# 2Leonardo_PCB.net
KiCad netlist of a schematic drawn in Altium Designer
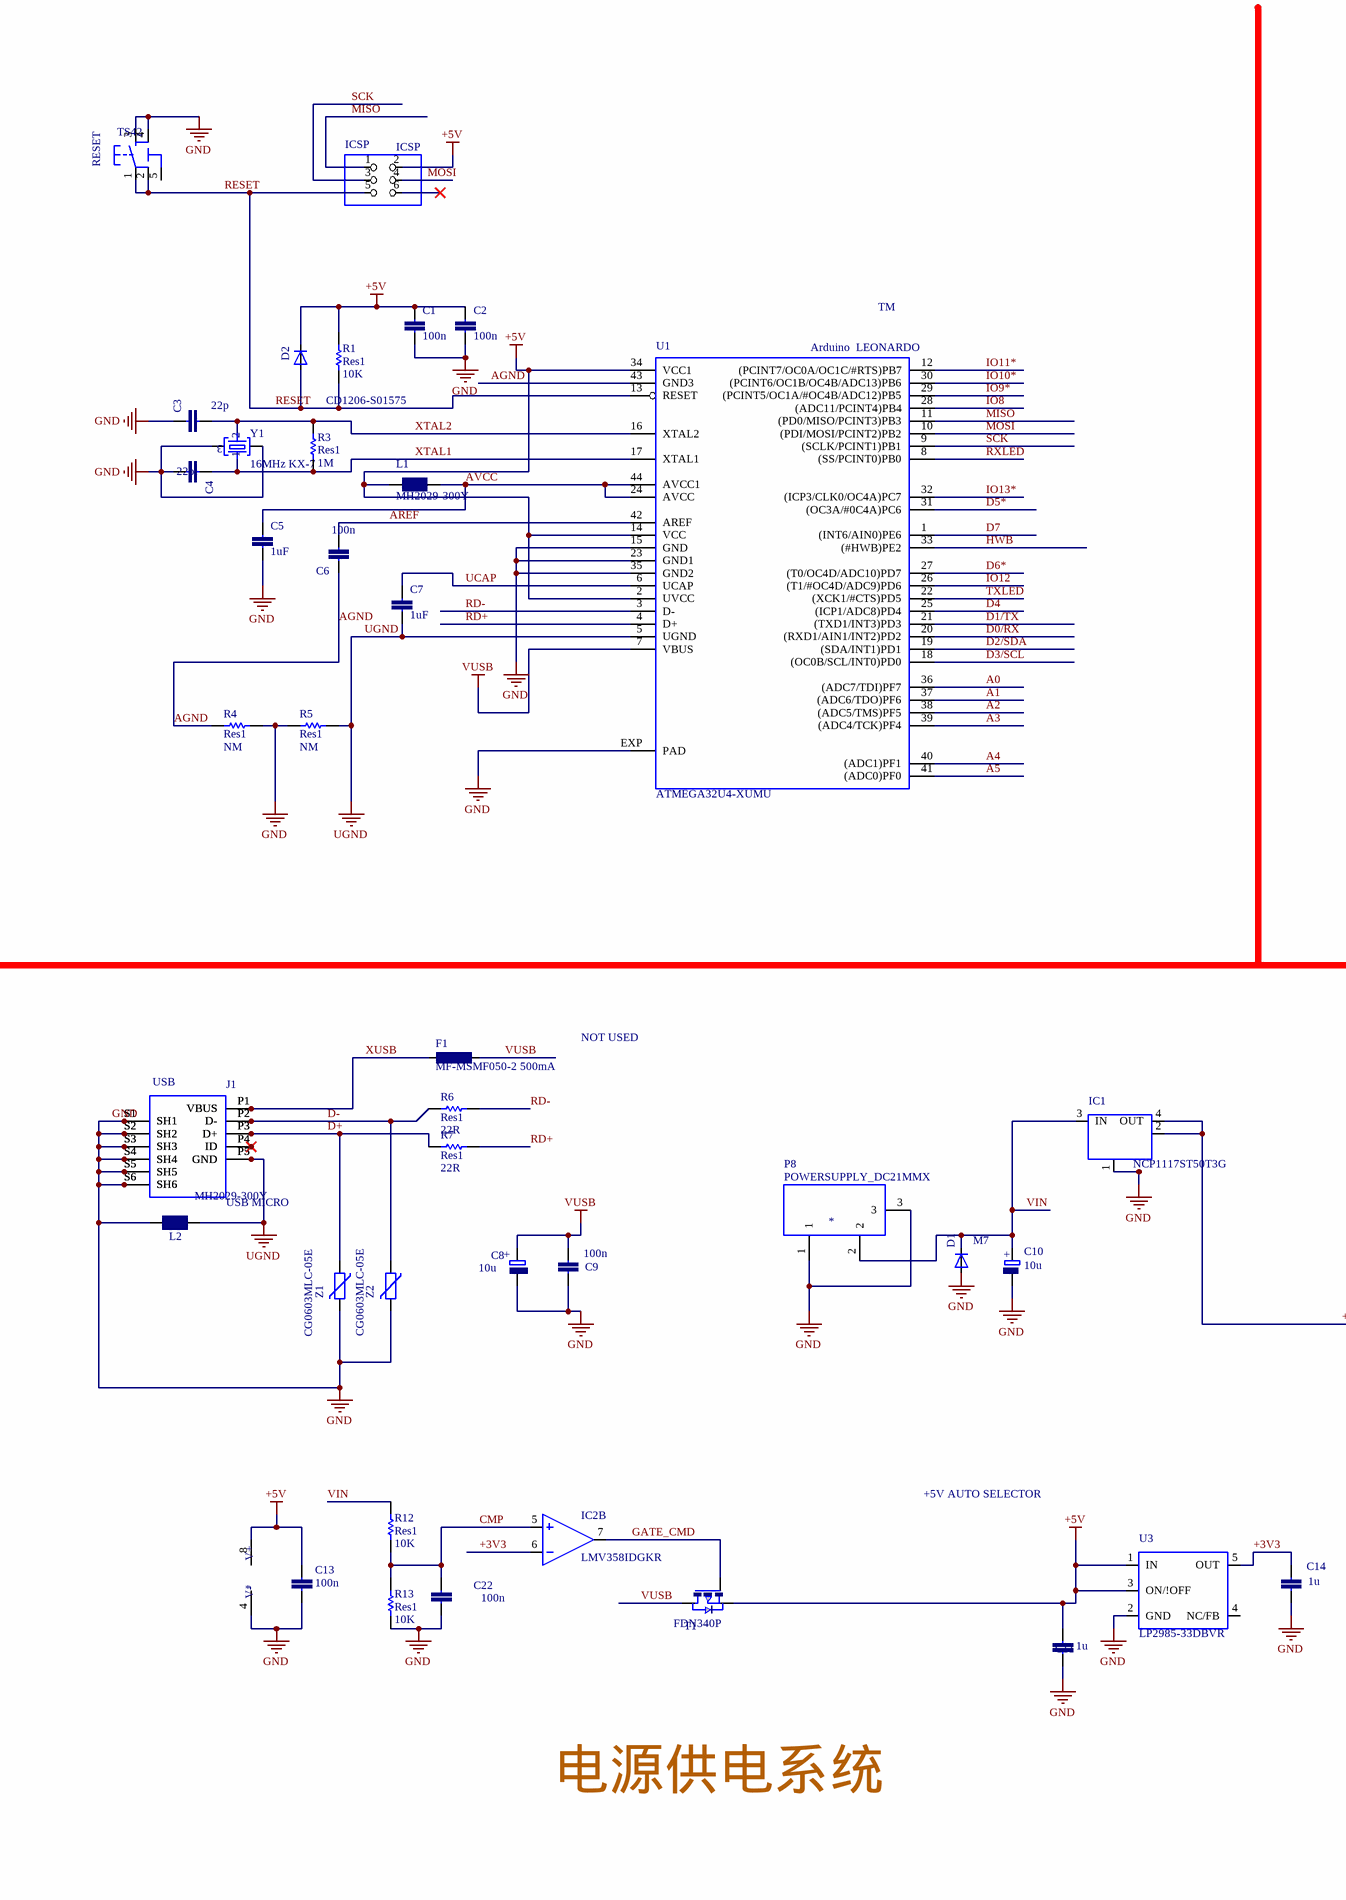
[diagram p0: 2Leonardo_PCB.SchDoc, left]
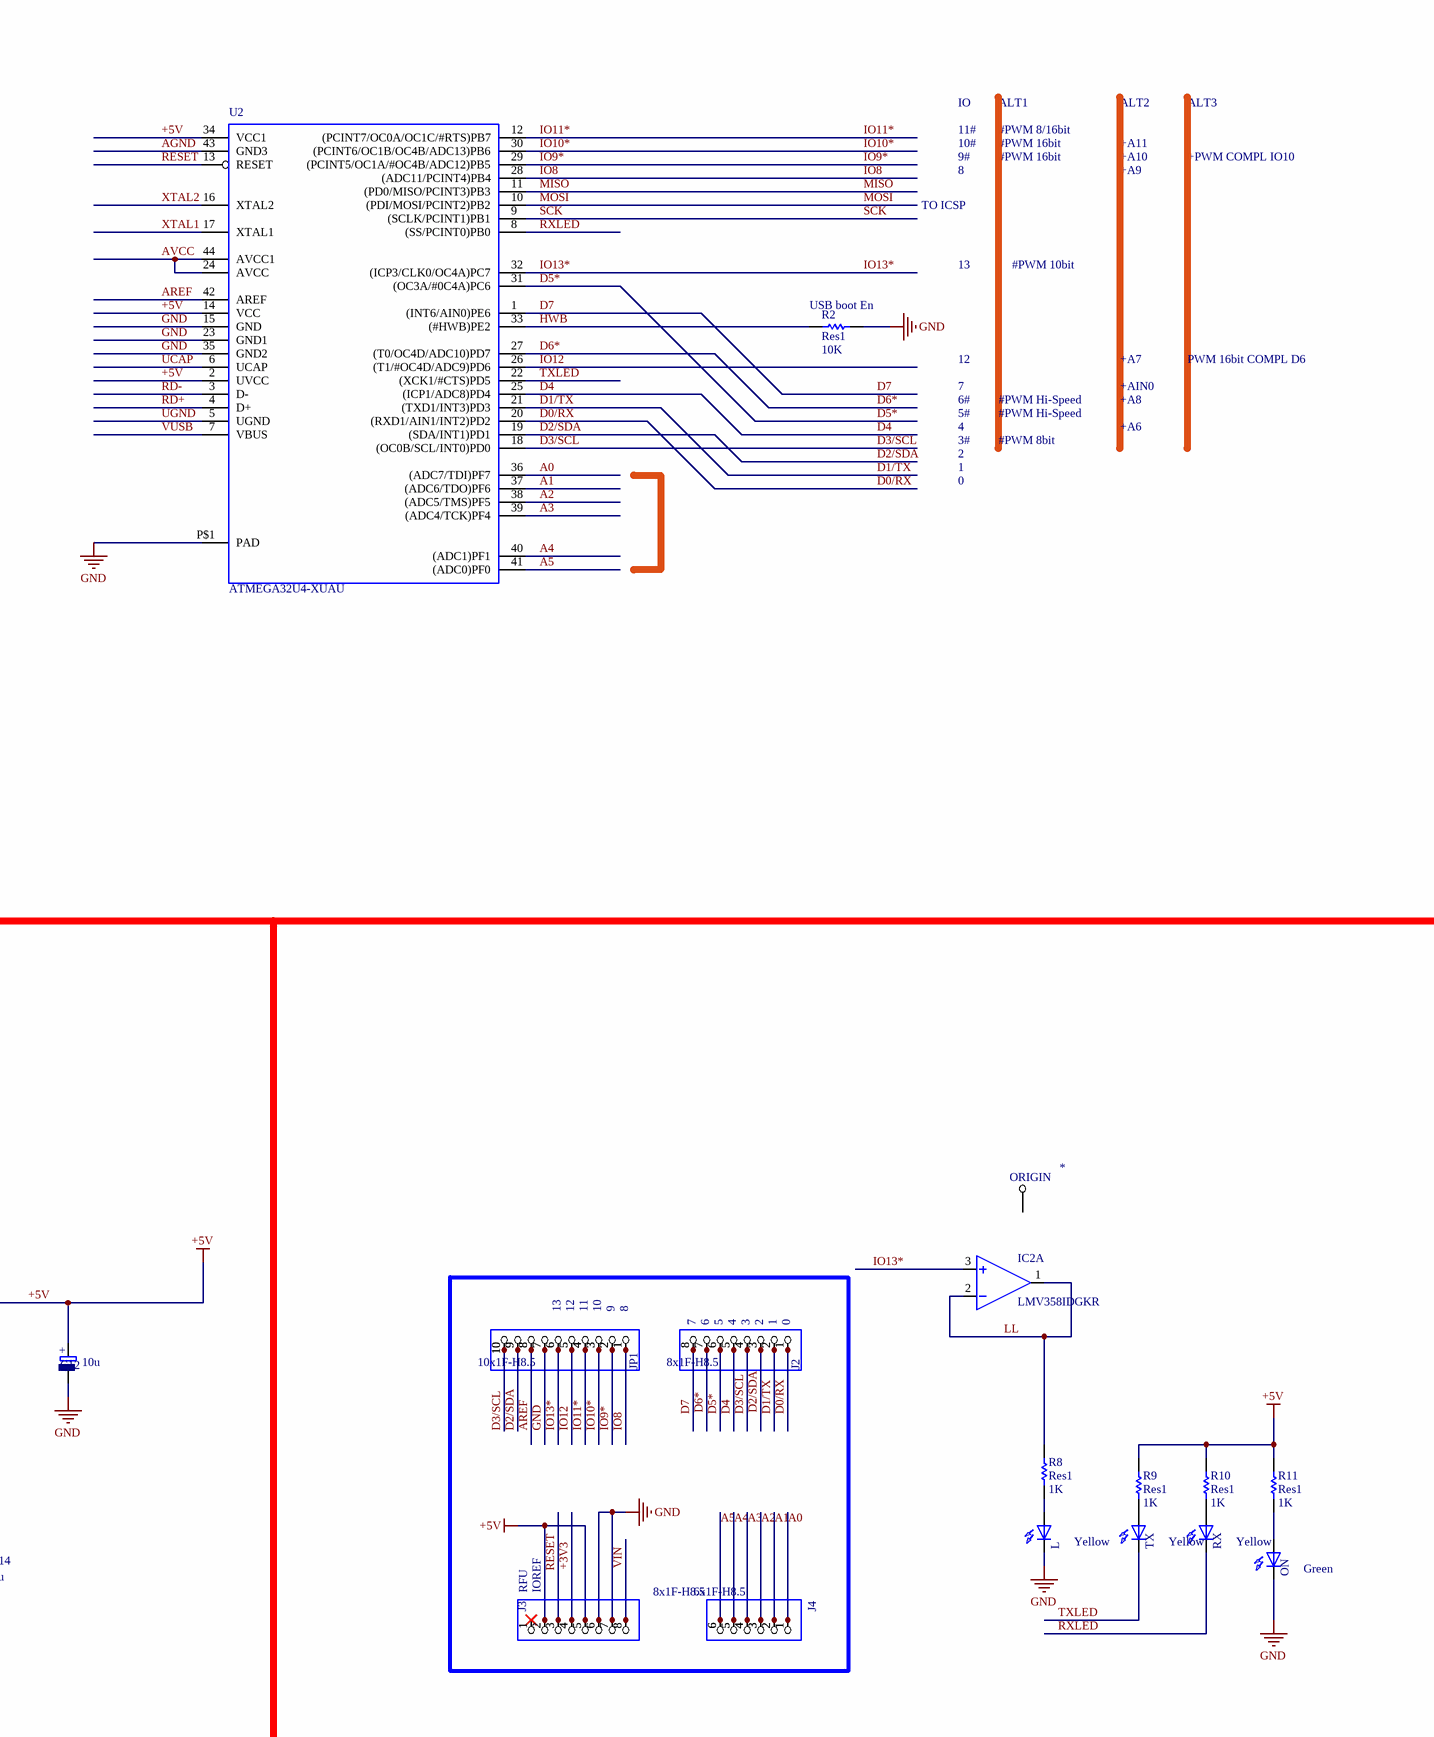
[diagram p1: 2Leonardo_PCB.SchDoc, right]

(export (version "E")
  (design (tool "Eeschema 10.0.6"))
  (components
    (comp (ref "C1") (value "100n") (footprint "C0603-ROUND") (libsource (lib "SmartPrj") (part "C-EUC0603")))
    (comp (ref "C2") (value "100n") (footprint "C0603-ROUND") (libsource (lib "SmartPrj") (part "C-EUC0603")))
    (comp (ref "C3") (value "22p") (footprint "C0603-ROUND") (libsource (lib "") (part "C-EUC0603_3")))
    (comp (ref "C4") (value "22p") (footprint "C0603-ROUND") (libsource (lib "") (part "C-EUC0603_1")))
    (comp (ref "C5") (value "1uF") (footprint "C0603-ROUND") (libsource (lib "SmartPrj") (part "C-EUC0603")))
    (comp (ref "C6") (value "100n") (footprint "C0603-ROUND") (libsource (lib "") (part "C-EUC0603_2")))
    (comp (ref "C7") (value "1uF") (footprint "C0603-ROUND") (libsource (lib "SmartPrj") (part "C-EUC0603")))
    (comp (ref "C8") (value "10u") (footprint "SMC_B") (libsource (lib "rcl") (part "CPOL-EUSMCB")))
    (comp (ref "C9") (value "100n") (footprint "C0603-ROUND") (libsource (lib "") (part "C-EUC0603_3")))
    (comp (ref "C10") (value "10u") (footprint "SMC_B") (libsource (lib "") (part "CPOL-EUSMCB_1")))
    (comp (ref "C11") (value "1u") (footprint "C0603-ROUND") (libsource (lib "") (part "C-EUC0603_3")))
    (comp (ref "C12") (value "10u") (footprint "SMC_B") (libsource (lib "") (part "CPOL-EUSMCB_1")))
    (comp (ref "C13")
      (value "100n")
      (footprint "C0603-ROUND")
      (libsource (lib "SmartPrj") (part "C-EUC0603"))
    )
    (comp (ref "C14") (value "1u") (footprint "C0603-ROUND") (libsource (lib "") (part "C-EUC0603_2")))
    (comp (ref "C22") (value "100n") (footprint "C0603-ROUND") (libsource (lib "") (part "C-EUC0603_3")))
    (comp (ref "D1") (value "M7") (footprint "SMB") (libsource (lib "diode") (part "DIODE-SMB")))
    (comp (ref "D2")
      (value "CD1206-S01575")
      (footprint "MINIMELF")
      (libsource (lib "diode") (part "DIODE-MINIMELF"))
    )
    (comp (ref "F1")
      (value "MF-MSMF050-2 500mA")
      (footprint "L1812")
      (libsource (lib "rcl") (part "L-EUL1812"))
    )
    (comp (ref "IC1")
      (value "NCP1117ST50T3G")
      (footprint "SOT223")
      (libsource (lib "linear") (part "MC33269ST-3.3T3"))
    )
    (comp (ref "IC2")
      (value "LMV358IDGKR")
      (footprint "MSOP08")
      (libsource (lib "linear") (part "LMV358MMX"))
    )
    (comp (ref "ICSP") (value "ICSP") (footprint "2X03") (libsource (lib "SmartPrj") (part "PINHD-2X3")))
    (comp (ref "J1")
      (value "USB MICRO")
      (footprint "CON2_USB_MICRO_B_AT")
      (libsource (lib "SmartPrj") (part "MYCON2_USB-MINI-B"))
    )
    (comp (ref "J2") (value "8x1F-H8.5") (footprint "1X08") (libsource (lib "SmartPrj") (part "PINHD-1X8")))
    (comp (ref "J3") (value "8x1F-H8.5") (footprint "1X08") (libsource (lib "SmartPrj") (part "PINHD-1X8")))
    (comp (ref "J4") (value "6x1F-H8.5") (footprint "1X06") (libsource (lib "SmartPrj") (part "PINHD-1X6")))
    (comp (ref "JP1")
      (value "10x1F-H8.5")
      (footprint "1X10")
      (libsource (lib "SmartPrj") (part "PINHD-1X10"))
    )
    (comp (ref "L")
      (value "Yellow")
      (footprint "CHIPLED_0805")
      (libsource (lib "led") (part "LEDCHIPLED_0805"))
    )
    (comp (ref "L1") (value "MH2029-300Y") (footprint "0805") (libsource (lib "") (part "WE-CBF_0805_1")))
    (comp (ref "L2")
      (value "MH2029-300Y")
      (footprint "0805")
      (libsource (lib "wuerth-elektronik") (part "WE-CBF_0805"))
    )
    (comp (ref "ON")
      (value "Green")
      (footprint "CHIPLED_0805")
      (libsource (lib "led") (part "LEDCHIPLED_0805"))
    )
    (comp (ref "ORIGIN") (value "*") (footprint "FIDUCIA-MOUNT") (libsource (lib "SmartPrj") (part "TP_SP")))
    (comp (ref "P8")
      (value "*")
      (footprint "POWERSUPPLY_DC-21MM")
      (libsource (lib "SmartPrj") (part "POWERSUPPLY_DC21MMX"))
    )
    (comp (ref "R1")
      (value "Res1")
      (footprint "R0603-ROUND")
      (description "Resistor")
      (fields (field (name "ALTIUM_VALUE") "10K") (field (name "PUBLISHER") "Altium Limited"))
      (libsource (lib "Miscellaneous Devices") (part "Res1"))
    )
    (comp (ref "R2")
      (value "Res1")
      (footprint "R0603-ROUND")
      (description "Resistor")
      (fields (field (name "ALTIUM_VALUE") "10K") (field (name "PUBLISHER") "Altium Limited"))
      (libsource (lib "Miscellaneous Devices") (part "Res1"))
    )
    (comp (ref "R3")
      (value "Res1")
      (footprint "R0603-ROUND")
      (description "Resistor")
      (fields (field (name "ALTIUM_VALUE") "1M") (field (name "PUBLISHER") "Altium Limited"))
      (libsource (lib "Miscellaneous Devices") (part "Res1"))
    )
    (comp (ref "R4")
      (value "Res1")
      (footprint "R0603-ROUND")
      (description "Resistor")
      (fields (field (name "ALTIUM_VALUE") "NM") (field (name "PUBLISHER") "Altium Limited"))
      (libsource (lib "Miscellaneous Devices") (part "Res1"))
    )
    (comp (ref "R5")
      (value "Res1")
      (footprint "R0603-ROUND")
      (description "Resistor")
      (fields (field (name "ALTIUM_VALUE") "NM") (field (name "PUBLISHER") "Altium Limited"))
      (libsource (lib "Miscellaneous Devices") (part "Res1"))
    )
    (comp (ref "R6")
      (value "Res1")
      (footprint "R0603-ROUND")
      (description "Resistor")
      (fields (field (name "ALTIUM_VALUE") "22R") (field (name "PUBLISHER") "Altium Limited"))
      (libsource (lib "Miscellaneous Devices") (part "Res1"))
    )
    (comp (ref "R7")
      (value "Res1")
      (footprint "R0603-ROUND")
      (description "Resistor")
      (fields (field (name "ALTIUM_VALUE") "22R") (field (name "PUBLISHER") "Altium Limited"))
      (libsource (lib "Miscellaneous Devices") (part "Res1"))
    )
    (comp (ref "R8")
      (value "Res1")
      (footprint "R0603-ROUND")
      (description "Resistor")
      (fields (field (name "ALTIUM_VALUE") "1K") (field (name "PUBLISHER") "Altium Limited"))
      (libsource (lib "Miscellaneous Devices") (part "Res1"))
    )
    (comp (ref "R9")
      (value "Res1")
      (footprint "R0603-ROUND")
      (description "Resistor")
      (fields (field (name "ALTIUM_VALUE") "1K") (field (name "PUBLISHER") "Altium Limited"))
      (libsource (lib "Miscellaneous Devices") (part "Res1"))
    )
    (comp (ref "R10")
      (value "Res1")
      (footprint "R0603-ROUND")
      (description "Resistor")
      (fields (field (name "ALTIUM_VALUE") "1K") (field (name "PUBLISHER") "Altium Limited"))
      (libsource (lib "Miscellaneous Devices") (part "Res1"))
    )
    (comp (ref "R11")
      (value "Res1")
      (footprint "R0603-ROUND")
      (description "Resistor")
      (fields (field (name "ALTIUM_VALUE") "1K") (field (name "PUBLISHER") "Altium Limited"))
      (libsource (lib "Miscellaneous Devices") (part "Res1"))
    )
    (comp (ref "R12")
      (value "Res1")
      (footprint "R0603-ROUND")
      (description "Resistor")
      (fields (field (name "ALTIUM_VALUE") "10K") (field (name "PUBLISHER") "Altium Limited"))
      (libsource (lib "Miscellaneous Devices") (part "Res1"))
    )
    (comp (ref "R13")
      (value "Res1")
      (footprint "R0603-ROUND")
      (description "Resistor")
      (fields (field (name "ALTIUM_VALUE") "10K") (field (name "PUBLISHER") "Altium Limited"))
      (libsource (lib "Miscellaneous Devices") (part "Res1"))
    )
    (comp (ref "RESET") (value "TS42") (footprint "TS42") (libsource (lib "SmartPrj") (part "TS42")))
    (comp (ref "RX")
      (value "Yellow")
      (footprint "CHIPLED_0805")
      (libsource (lib "led") (part "LEDCHIPLED_0805"))
    )
    (comp (ref "T1") (value "FDN340P") (footprint "SOT-23") (libsource (lib "zetex") (part "PMOSSOT23")))
    (comp (ref "TX")
      (value "Yellow")
      (footprint "CHIPLED_0805")
      (libsource (lib "led") (part "LEDCHIPLED_0805"))
    )
    (comp (ref "U1")
      (value "ATMEGA32U4-XUMU")
      (footprint "QFN44ML7X7")
      (libsource (lib "SmartPrj") (part "ATMEGA32U4-XUMU"))
    )
    (comp (ref "U2")
      (value "ATMEGA32U4-XUAU")
      (footprint "TQFP44-PAD")
      (libsource (lib "SmartPrj") (part "ATMEGA32U4-XUAU"))
    )
    (comp (ref "U3")
      (value "LP2985-33DBVR")
      (footprint "SOT23-DBV")
      (libsource (lib "SmartPrj") (part "LP2985-XXDBVR33"))
    )
    (comp (ref "Y1")
      (value "16MHz KX-7")
      (footprint "CRYSTAL-3.2-2.5")
      (libsource (lib "SmartPrj") (part "CRYSTAL-3.2-2.5"))
    )
    (comp (ref "Z1")
      (value "CG0603MLC-05E")
      (footprint "CT/CN0603")
      (libsource (lib "varistor") (part "VARISTORCN0603"))
    )
    (comp (ref "Z2")
      (value "CG0603MLC-05E")
      (footprint "CT/CN0603")
      (libsource (lib "varistor") (part "VARISTORCN0603"))
    )
  )
  (nets
    (net (code "1") (name "+5V") (class "Default")
      (node (ref "C1") (pin "1") (pinfunction "1_1") (pintype "passive"))
      (node (ref "C11") (pin "2") (pinfunction "2_2") (pintype "passive"))
      (node (ref "C12") (pin "+") (pinfunction "+_+") (pintype "passive"))
      (node (ref "C13") (pin "1") (pinfunction "1_1") (pintype "passive"))
      (node (ref "C2") (pin "1") (pinfunction "1_1") (pintype "passive"))
      (node (ref "D2") (pin "C") (pinfunction "C_C") (pintype "passive"))
      (node (ref "IC1") (pin "2") (pinfunction "OUT@1_2") (pintype "passive"))
      (node (ref "IC1") (pin "4") (pinfunction "OUT_4") (pintype "passive"))
      (node (ref "IC2") (pin "8") (pinfunction "V+_8") (pintype "passive"))
      (node (ref "ICSP") (pin "2") (pinfunction "2_2") (pintype "passive"))
      (node (ref "J3") (pin "2") (pinfunction "2_2") (pintype "passive"))
      (node (ref "J3") (pin "5") (pinfunction "5_5") (pintype "passive"))
      (node (ref "L1") (pin "1") (pinfunction "1_1") (pintype "passive"))
      (node (ref "R1") (pin "2") (pinfunction "2_2") (pintype "passive"))
      (node (ref "R10") (pin "2") (pinfunction "2_2") (pintype "passive"))
      (node (ref "R11") (pin "2") (pinfunction "2_2") (pintype "passive"))
      (node (ref "R9") (pin "2") (pinfunction "2_2") (pintype "passive"))
      (node (ref "T1") (pin "2") (pinfunction "S_2") (pintype "passive"))
      (node (ref "U1") (pin "14") (pinfunction "VCC_14") (pintype "passive"))
      (node (ref "U1") (pin "2") (pinfunction "UVCC_2") (pintype "passive"))
      (node (ref "U1") (pin "34") (pinfunction "VCC1_34") (pintype "passive"))
      (node (ref "U2") (pin "14") (pinfunction "VCC_14") (pintype "passive"))
      (node (ref "U2") (pin "2") (pinfunction "UVCC_2") (pintype "passive"))
      (node (ref "U2") (pin "34") (pinfunction "VCC1_34") (pintype "passive"))
      (node (ref "U3") (pin "1") (pinfunction "IN_1") (pintype "passive"))
      (node (ref "U3") (pin "3") (pinfunction "ON/!OFF_3") (pintype "passive"))
    )
    (net (code "2") (name "/+3V3") (class "Default")
      (node (ref "C14") (pin "2") (pinfunction "2_2") (pintype "passive"))
      (node (ref "IC2") (pin "6") (pinfunction "-IN_6") (pintype "passive"))
      (node (ref "J3") (pin "4") (pinfunction "4_4") (pintype "passive"))
      (node (ref "U3") (pin "5") (pinfunction "OUT_5") (pintype "passive"))
    )
    (net (code "3") (name "/A0") (class "Default")
      (node (ref "J4") (pin "1") (pinfunction "1_1") (pintype "passive"))
      (node (ref "U1") (pin "36") (pinfunction "(ADC7/TDI)PF7_36") (pintype "passive"))
      (node (ref "U2") (pin "36") (pinfunction "(ADC7/TDI)PF7_36") (pintype "passive"))
    )
    (net (code "4") (name "/A1") (class "Default")
      (node (ref "J4") (pin "2") (pinfunction "2_2") (pintype "passive"))
      (node (ref "U1") (pin "37") (pinfunction "(ADC6/TDO)PF6_37") (pintype "passive"))
      (node (ref "U2") (pin "37") (pinfunction "(ADC6/TDO)PF6_37") (pintype "passive"))
    )
    (net (code "5") (name "/A2") (class "Default")
      (node (ref "J4") (pin "3") (pinfunction "3_3") (pintype "passive"))
      (node (ref "U1") (pin "38") (pinfunction "(ADC5/TMS)PF5_38") (pintype "passive"))
      (node (ref "U2") (pin "38") (pinfunction "(ADC5/TMS)PF5_38") (pintype "passive"))
    )
    (net (code "6") (name "/A3") (class "Default")
      (node (ref "J4") (pin "4") (pinfunction "4_4") (pintype "passive"))
      (node (ref "U1") (pin "39") (pinfunction "(ADC4/TCK)PF4_39") (pintype "passive"))
      (node (ref "U2") (pin "39") (pinfunction "(ADC4/TCK)PF4_39") (pintype "passive"))
    )
    (net (code "7") (name "/A4") (class "Default")
      (node (ref "J4") (pin "5") (pinfunction "5_5") (pintype "passive"))
      (node (ref "U1") (pin "40") (pinfunction "(ADC1)PF1_40") (pintype "passive"))
      (node (ref "U2") (pin "40") (pinfunction "(ADC1)PF1_40") (pintype "passive"))
    )
    (net (code "8") (name "/A5") (class "Default")
      (node (ref "J4") (pin "6") (pinfunction "6_6") (pintype "passive"))
      (node (ref "U1") (pin "41") (pinfunction "(ADC0)PF0_41") (pintype "passive"))
      (node (ref "U2") (pin "41") (pinfunction "(ADC0)PF0_41") (pintype "passive"))
    )
    (net (code "9") (name "/AGND") (class "Default")
      (node (ref "C6") (pin "1") (pinfunction "1_1") (pintype "passive"))
      (node (ref "R4") (pin "1") (pinfunction "1_1") (pintype "passive"))
      (node (ref "U1") (pin "43") (pinfunction "GND3_43") (pintype "passive"))
      (node (ref "U2") (pin "43") (pinfunction "GND3_43") (pintype "passive"))
    )
    (net (code "10") (name "/AREF") (class "Default")
      (node (ref "C6") (pin "2") (pinfunction "2_2") (pintype "passive"))
      (node (ref "JP1") (pin "8") (pinfunction "8_8") (pintype "passive"))
      (node (ref "U1") (pin "42") (pinfunction "AREF_42") (pintype "passive"))
      (node (ref "U2") (pin "42") (pinfunction "AREF_42") (pintype "passive"))
    )
    (net (code "11") (name "/AVCC") (class "Default")
      (node (ref "C5") (pin "1") (pinfunction "1_1") (pintype "passive"))
      (node (ref "L1") (pin "2") (pinfunction "2_2") (pintype "passive"))
      (node (ref "U1") (pin "24") (pinfunction "AVCC_24") (pintype "passive"))
      (node (ref "U1") (pin "44") (pinfunction "AVCC1_44") (pintype "passive"))
      (node (ref "U2") (pin "24") (pinfunction "AVCC_24") (pintype "passive"))
      (node (ref "U2") (pin "44") (pinfunction "AVCC1_44") (pintype "passive"))
    )
    (net (code "12") (name "/CMP") (class "Default")
      (node (ref "C22") (pin "2") (pinfunction "2_2") (pintype "passive"))
      (node (ref "IC2") (pin "5") (pinfunction "+IN_5") (pintype "passive"))
      (node (ref "R12") (pin "1") (pinfunction "1_1") (pintype "passive"))
      (node (ref "R13") (pin "2") (pinfunction "2_2") (pintype "passive"))
    )
    (net (code "13") (name "/D+") (class "Default")
      (node (ref "J1") (pin "P3") (pinfunction "D+_P3") (pintype "passive"))
      (node (ref "R7") (pin "1") (pinfunction "1_1") (pintype "passive"))
      (node (ref "Z1") (pin "1") (pinfunction "1_1") (pintype "passive"))
    )
    (net (code "14") (name "/D-") (class "Default")
      (node (ref "J1") (pin "P2") (pinfunction "D-_P2") (pintype "passive"))
      (node (ref "R6") (pin "1") (pinfunction "1_1") (pintype "passive"))
      (node (ref "Z2") (pin "1") (pinfunction "1_1") (pintype "passive"))
    )
    (net (code "15") (name "/D0{slash}RX") (class "Default")
      (node (ref "J2") (pin "1") (pinfunction "1_1") (pintype "passive"))
      (node (ref "U1") (pin "20") (pinfunction "(RXD1/AIN1/INT2)PD2_20") (pintype "passive"))
      (node (ref "U2") (pin "20") (pinfunction "(RXD1/AIN1/INT2)PD2_20") (pintype "passive"))
    )
    (net (code "16") (name "/D1{slash}TX") (class "Default")
      (node (ref "J2") (pin "2") (pinfunction "2_2") (pintype "passive"))
      (node (ref "U1") (pin "21") (pinfunction "(TXD1/INT3)PD3_21") (pintype "passive"))
      (node (ref "U2") (pin "21") (pinfunction "(TXD1/INT3)PD3_21") (pintype "passive"))
    )
    (net (code "17") (name "/D2{slash}SDA") (class "Default")
      (node (ref "J2") (pin "3") (pinfunction "3_3") (pintype "passive"))
      (node (ref "JP1") (pin "9") (pinfunction "9_9") (pintype "passive"))
      (node (ref "U1") (pin "19") (pinfunction "(SDA/INT1)PD1_19") (pintype "passive"))
      (node (ref "U2") (pin "19") (pinfunction "(SDA/INT1)PD1_19") (pintype "passive"))
    )
    (net (code "18") (name "/D3{slash}SCL") (class "Default")
      (node (ref "J2") (pin "4") (pinfunction "4_4") (pintype "passive"))
      (node (ref "JP1") (pin "10") (pinfunction "10_10") (pintype "passive"))
      (node (ref "U1") (pin "18") (pinfunction "(OC0B/SCL/INT0)PD0_18") (pintype "passive"))
      (node (ref "U2") (pin "18") (pinfunction "(OC0B/SCL/INT0)PD0_18") (pintype "passive"))
    )
    (net (code "19") (name "/D4") (class "Default")
      (node (ref "J2") (pin "5") (pinfunction "5_5") (pintype "passive"))
      (node (ref "U1") (pin "25") (pinfunction "(ICP1/ADC8)PD4_25") (pintype "passive"))
      (node (ref "U2") (pin "25") (pinfunction "(ICP1/ADC8)PD4_25") (pintype "passive"))
    )
    (net (code "20") (name "/D5*") (class "Default")
      (node (ref "J2") (pin "6") (pinfunction "6_6") (pintype "passive"))
      (node (ref "U1") (pin "31") (pinfunction "(OC3A/#0C4A)PC6_31") (pintype "passive"))
      (node (ref "U2") (pin "31") (pinfunction "(OC3A/#0C4A)PC6_31") (pintype "passive"))
    )
    (net (code "21") (name "/D6*") (class "Default")
      (node (ref "J2") (pin "7") (pinfunction "7_7") (pintype "passive"))
      (node (ref "U1") (pin "27") (pinfunction "(T0/OC4D/ADC10)PD7_27") (pintype "passive"))
      (node (ref "U2") (pin "27") (pinfunction "(T0/OC4D/ADC10)PD7_27") (pintype "passive"))
    )
    (net (code "22") (name "/D7") (class "Default")
      (node (ref "J2") (pin "8") (pinfunction "8_8") (pintype "passive"))
      (node (ref "U1") (pin "1") (pinfunction "(INT6/AIN0)PE6_1") (pintype "passive"))
      (node (ref "U2") (pin "1") (pinfunction "(INT6/AIN0)PE6_1") (pintype "passive"))
    )
    (net (code "23") (name "/GATE_CMD") (class "Default")
      (node (ref "IC2") (pin "7") (pinfunction "OUT_7") (pintype "passive"))
      (node (ref "T1") (pin "3") (pinfunction "G_3") (pintype "passive"))
    )
    (net (code "24") (name "/HWB") (class "Default")
      (node (ref "R2") (pin "2") (pinfunction "2_2") (pintype "passive"))
      (node (ref "U1") (pin "33") (pinfunction "(#HWB)PE2_33") (pintype "passive"))
      (node (ref "U2") (pin "33") (pinfunction "(#HWB)PE2_33") (pintype "passive"))
    )
    (net (code "25") (name "/IO8") (class "Default")
      (node (ref "JP1") (pin "1") (pinfunction "1_1") (pintype "passive"))
      (node (ref "U1") (pin "28") (pinfunction "(ADC11/PCINT4)PB4_28") (pintype "passive"))
      (node (ref "U2") (pin "28") (pinfunction "(ADC11/PCINT4)PB4_28") (pintype "passive"))
    )
    (net (code "26") (name "/IO9*") (class "Default")
      (node (ref "JP1") (pin "2") (pinfunction "2_2") (pintype "passive"))
      (node (ref "U1") (pin "29") (pinfunction "(PCINT5/OC1A/#OC4B/ADC12)PB5_29") (pintype "passive"))
      (node (ref "U2") (pin "29") (pinfunction "(PCINT5/OC1A/#OC4B/ADC12)PB5_29") (pintype "passive"))
    )
    (net (code "27") (name "/IO10*") (class "Default")
      (node (ref "JP1") (pin "3") (pinfunction "3_3") (pintype "passive"))
      (node (ref "U1") (pin "30") (pinfunction "(PCINT6/OC1B/OC4B/ADC13)PB6_30") (pintype "passive"))
      (node (ref "U2") (pin "30") (pinfunction "(PCINT6/OC1B/OC4B/ADC13)PB6_30") (pintype "passive"))
    )
    (net (code "28") (name "/IO11*") (class "Default")
      (node (ref "JP1") (pin "4") (pinfunction "4_4") (pintype "passive"))
      (node (ref "U1") (pin "12") (pinfunction "(PCINT7/OC0A/OC1C/#RTS)PB7_12") (pintype "passive"))
      (node (ref "U2") (pin "12") (pinfunction "(PCINT7/OC0A/OC1C/#RTS)PB7_12") (pintype "passive"))
    )
    (net (code "29") (name "/IO12") (class "Default")
      (node (ref "JP1") (pin "5") (pinfunction "5_5") (pintype "passive"))
      (node (ref "U1") (pin "26") (pinfunction "(T1/#OC4D/ADC9)PD6_26") (pintype "passive"))
      (node (ref "U2") (pin "26") (pinfunction "(T1/#OC4D/ADC9)PD6_26") (pintype "passive"))
    )
    (net (code "30") (name "/IO13*") (class "Default")
      (node (ref "IC2") (pin "3") (pinfunction "+IN_3") (pintype "passive"))
      (node (ref "JP1") (pin "6") (pinfunction "6_6") (pintype "passive"))
      (node (ref "U1") (pin "32") (pinfunction "(ICP3/CLK0/OC4A)PC7_32") (pintype "passive"))
      (node (ref "U2") (pin "32") (pinfunction "(ICP3/CLK0/OC4A)PC7_32") (pintype "passive"))
    )
    (net (code "31") (name "/LL") (class "Default")
      (node (ref "IC2") (pin "1") (pinfunction "OUT_1") (pintype "passive"))
      (node (ref "IC2") (pin "2") (pinfunction "-IN_2") (pintype "passive"))
      (node (ref "R8") (pin "2") (pinfunction "2_2") (pintype "passive"))
    )
    (net (code "32") (name "/MISO") (class "Default")
      (node (ref "ICSP") (pin "1") (pinfunction "1_1") (pintype "passive"))
      (node (ref "U1") (pin "11") (pinfunction "(PD0/MISO/PCINT3)PB3_11") (pintype "passive"))
      (node (ref "U2") (pin "11") (pinfunction "(PD0/MISO/PCINT3)PB3_11") (pintype "passive"))
    )
    (net (code "33") (name "/MOSI") (class "Default")
      (node (ref "ICSP") (pin "4") (pinfunction "4_4") (pintype "passive"))
      (node (ref "U1") (pin "10") (pinfunction "(PDI/MOSI/PCINT2)PB2_10") (pintype "passive"))
      (node (ref "U2") (pin "10") (pinfunction "(PDI/MOSI/PCINT2)PB2_10") (pintype "passive"))
    )
    (net (code "34") (name "/RD+") (class "Default")
      (node (ref "R7") (pin "2") (pinfunction "2_2") (pintype "passive"))
      (node (ref "U1") (pin "4") (pinfunction "D+_4") (pintype "passive"))
      (node (ref "U2") (pin "4") (pinfunction "D+_4") (pintype "passive"))
    )
    (net (code "35") (name "/RD-") (class "Default")
      (node (ref "R6") (pin "2") (pinfunction "2_2") (pintype "passive"))
      (node (ref "U1") (pin "3") (pinfunction "D-_3") (pintype "passive"))
      (node (ref "U2") (pin "3") (pinfunction "D-_3") (pintype "passive"))
    )
    (net (code "36") (name "/RESET") (class "Default")
      (node (ref "D2") (pin "A") (pinfunction "A_A") (pintype "passive"))
      (node (ref "ICSP") (pin "5") (pinfunction "5_5") (pintype "passive"))
      (node (ref "J3") (pin "3") (pinfunction "3_3") (pintype "passive"))
      (node (ref "R1") (pin "1") (pinfunction "1_1") (pintype "passive"))
      (node (ref "RESET") (pin "1") (pinfunction "1_1") (pintype "passive"))
      (node (ref "RESET") (pin "2") (pinfunction "2_2") (pintype "passive"))
      (node (ref "U1") (pin "13") (pinfunction "RESET_13") (pintype "passive"))
      (node (ref "U2") (pin "13") (pinfunction "RESET_13") (pintype "passive"))
    )
    (net (code "37") (name "/RXLED") (class "Default")
      (node (ref "RX") (pin "C") (pinfunction "C_C") (pintype "passive"))
      (node (ref "U1") (pin "8") (pinfunction "(SS/PCINT0)PB0_8") (pintype "passive"))
      (node (ref "U2") (pin "8") (pinfunction "(SS/PCINT0)PB0_8") (pintype "passive"))
    )
    (net (code "38") (name "/SCK") (class "Default")
      (node (ref "ICSP") (pin "3") (pinfunction "3_3") (pintype "passive"))
      (node (ref "U1") (pin "9") (pinfunction "(SCLK/PCINT1)PB1_9") (pintype "passive"))
      (node (ref "U2") (pin "9") (pinfunction "(SCLK/PCINT1)PB1_9") (pintype "passive"))
    )
    (net (code "39") (name "/TXLED") (class "Default")
      (node (ref "TX") (pin "C") (pinfunction "C_C") (pintype "passive"))
      (node (ref "U1") (pin "22") (pinfunction "(XCK1/#CTS)PD5_22") (pintype "passive"))
      (node (ref "U2") (pin "22") (pinfunction "(XCK1/#CTS)PD5_22") (pintype "passive"))
    )
    (net (code "40") (name "/UCAP") (class "Default")
      (node (ref "C7") (pin "1") (pinfunction "1_1") (pintype "passive"))
      (node (ref "U1") (pin "6") (pinfunction "UCAP_6") (pintype "passive"))
      (node (ref "U2") (pin "6") (pinfunction "UCAP_6") (pintype "passive"))
    )
    (net (code "41") (name "/VIN") (class "Default")
      (node (ref "C10") (pin "+") (pinfunction "+_+") (pintype "passive"))
      (node (ref "D1") (pin "C") (pinfunction "C_C") (pintype "passive"))
      (node (ref "IC1") (pin "3") (pinfunction "IN_3") (pintype "passive"))
      (node (ref "J3") (pin "8") (pinfunction "8_8") (pintype "passive"))
      (node (ref "P8") (pin "2") (pinfunction "2_2") (pintype "passive"))
      (node (ref "R12") (pin "2") (pinfunction "2_2") (pintype "passive"))
    )
    (net (code "42") (name "/XTAL1") (class "Default")
      (node (ref "C4") (pin "1") (pinfunction "1_1") (pintype "passive"))
      (node (ref "R3") (pin "1") (pinfunction "1_1") (pintype "passive"))
      (node (ref "U1") (pin "17") (pinfunction "XTAL1_17") (pintype "passive"))
      (node (ref "U2") (pin "17") (pinfunction "XTAL1_17") (pintype "passive"))
      (node (ref "Y1") (pin "1") (pinfunction "C1_1") (pintype "passive"))
    )
    (net (code "43") (name "/XTAL2") (class "Default")
      (node (ref "C3") (pin "2") (pinfunction "2_2") (pintype "passive"))
      (node (ref "R3") (pin "2") (pinfunction "2_2") (pintype "passive"))
      (node (ref "U1") (pin "16") (pinfunction "XTAL2_16") (pintype "passive"))
      (node (ref "U2") (pin "16") (pinfunction "XTAL2_16") (pintype "passive"))
      (node (ref "Y1") (pin "3") (pinfunction "C2_3") (pintype "passive"))
    )
    (net (code "44") (name "/XUSB") (class "Default")
      (node (ref "F1") (pin "2") (pinfunction "2_2") (pintype "passive"))
      (node (ref "J1") (pin "P1") (pinfunction "VBUS_P1") (pintype "passive"))
    )
    (net (code "45") (name "GND") (class "Default")
      (node (ref "C1") (pin "2") (pinfunction "2_2") (pintype "passive"))
      (node (ref "C10") (pin "-") (pinfunction "-_-") (pintype "passive"))
      (node (ref "C11") (pin "1") (pinfunction "1_1") (pintype "passive"))
      (node (ref "C12") (pin "-") (pinfunction "-_-") (pintype "passive"))
      (node (ref "C13") (pin "2") (pinfunction "2_2") (pintype "passive"))
      (node (ref "C14") (pin "1") (pinfunction "1_1") (pintype "passive"))
      (node (ref "C2") (pin "2") (pinfunction "2_2") (pintype "passive"))
      (node (ref "C22") (pin "1") (pinfunction "1_1") (pintype "passive"))
      (node (ref "C3") (pin "1") (pinfunction "1_1") (pintype "passive"))
      (node (ref "C4") (pin "2") (pinfunction "2_2") (pintype "passive"))
      (node (ref "C5") (pin "2") (pinfunction "2_2") (pintype "passive"))
      (node (ref "C8") (pin "-") (pinfunction "-_-") (pintype "passive"))
      (node (ref "C9") (pin "1") (pinfunction "1_1") (pintype "passive"))
      (node (ref "D1") (pin "A") (pinfunction "A_A") (pintype "passive"))
      (node (ref "IC1") (pin "1") (pinfunction "GND/ADJ_1") (pintype "passive"))
      (node (ref "IC2") (pin "4") (pinfunction "V-_4") (pintype "passive"))
      (node (ref "J1") (pin "S1") (pinfunction "SH1_S1") (pintype "passive"))
      (node (ref "J1") (pin "S2") (pinfunction "SH2_S2") (pintype "passive"))
      (node (ref "J1") (pin "S3") (pinfunction "SH3_S3") (pintype "passive"))
      (node (ref "J1") (pin "S4") (pinfunction "SH4_S4") (pintype "passive"))
      (node (ref "J1") (pin "S5") (pinfunction "SH5_S5") (pintype "passive"))
      (node (ref "J1") (pin "S6") (pinfunction "SH6_S6") (pintype "passive"))
      (node (ref "J3") (pin "6") (pinfunction "6_6") (pintype "passive"))
      (node (ref "J3") (pin "7") (pinfunction "7_7") (pintype "passive"))
      (node (ref "JP1") (pin "7") (pinfunction "7_7") (pintype "passive"))
      (node (ref "L") (pin "C") (pinfunction "C_C") (pintype "passive"))
      (node (ref "L2") (pin "2") (pinfunction "2_2") (pintype "passive"))
      (node (ref "ON") (pin "C") (pinfunction "C_C") (pintype "passive"))
      (node (ref "P8") (pin "1") (pinfunction "1_1") (pintype "passive"))
      (node (ref "P8") (pin "3") (pinfunction "3_3") (pintype "passive"))
      (node (ref "R13") (pin "1") (pinfunction "1_1") (pintype "passive"))
      (node (ref "R2") (pin "1") (pinfunction "1_1") (pintype "passive"))
      (node (ref "R4") (pin "2") (pinfunction "2_2") (pintype "passive"))
      (node (ref "R5") (pin "1") (pinfunction "1_1") (pintype "passive"))
      (node (ref "RESET") (pin "3") (pinfunction "3_3") (pintype "passive"))
      (node (ref "RESET") (pin "4") (pinfunction "4_4") (pintype "passive"))
      (node (ref "U1") (pin "15") (pinfunction "GND_15") (pintype "passive"))
      (node (ref "U1") (pin "23") (pinfunction "GND1_23") (pintype "passive"))
      (node (ref "U1") (pin "35") (pinfunction "GND2_35") (pintype "passive"))
      (node (ref "U1") (pin "EXP") (pinfunction "PAD_EXP") (pintype "passive"))
      (node (ref "U2") (pin "15") (pinfunction "GND_15") (pintype "passive"))
      (node (ref "U2") (pin "23") (pinfunction "GND1_23") (pintype "passive"))
      (node (ref "U2") (pin "35") (pinfunction "GND2_35") (pintype "passive"))
      (node (ref "U2") (pin "P$1") (pinfunction "PAD_P$1") (pintype "passive"))
      (node (ref "U3") (pin "2") (pinfunction "GND_2") (pintype "passive"))
      (node (ref "Y1") (pin "2") (pinfunction "GND@1_2") (pintype "passive"))
      (node (ref "Y1") (pin "4") (pinfunction "GND@2_4") (pintype "passive"))
      (node (ref "Z1") (pin "2") (pinfunction "2_2") (pintype "passive"))
      (node (ref "Z2") (pin "2") (pinfunction "2_2") (pintype "passive"))
    )
    (net (code "46") (name "Net-(L-PadA)") (class "Default")
      (node (ref "L") (pin "A") (pinfunction "A_A") (pintype "passive"))
      (node (ref "R8") (pin "1") (pinfunction "1_1") (pintype "passive"))
    )
    (net (code "47") (name "Net-(ON-PadA)") (class "Default")
      (node (ref "ON") (pin "A") (pinfunction "A_A") (pintype "passive"))
      (node (ref "R11") (pin "1") (pinfunction "1_1") (pintype "passive"))
    )
    (net (code "48") (name "Net-(R9-Pad1)") (class "Default")
      (node (ref "R9") (pin "1") (pinfunction "1_1") (pintype "passive"))
      (node (ref "TX") (pin "A") (pinfunction "A_A") (pintype "passive"))
    )
    (net (code "49") (name "Net-(R10-Pad1)") (class "Default")
      (node (ref "R10") (pin "1") (pinfunction "1_1") (pintype "passive"))
      (node (ref "RX") (pin "A") (pinfunction "A_A") (pintype "passive"))
    )
    (net (code "50") (name "UGND") (class "Default")
      (node (ref "C7") (pin "2") (pinfunction "2_2") (pintype "passive"))
      (node (ref "J1") (pin "P5") (pinfunction "GND_P5") (pintype "passive"))
      (node (ref "L2") (pin "1") (pinfunction "1_1") (pintype "passive"))
      (node (ref "R5") (pin "2") (pinfunction "2_2") (pintype "passive"))
      (node (ref "U1") (pin "5") (pinfunction "UGND_5") (pintype "passive"))
      (node (ref "U2") (pin "5") (pinfunction "UGND_5") (pintype "passive"))
    )
    (net (code "51") (name "VUSB") (class "Default")
      (node (ref "C8") (pin "+") (pinfunction "+_+") (pintype "passive"))
      (node (ref "C9") (pin "2") (pinfunction "2_2") (pintype "passive"))
      (node (ref "F1") (pin "1") (pinfunction "1_1") (pintype "passive"))
      (node (ref "T1") (pin "1") (pinfunction "D_1") (pintype "passive"))
      (node (ref "U1") (pin "7") (pinfunction "VBUS_7") (pintype "passive"))
      (node (ref "U2") (pin "7") (pinfunction "VBUS_7") (pintype "passive"))
    )
    (net (code "52") (name "unconnected-(ICSP-Pad6)") (class "Default")
      (node (ref "ICSP") (pin "6") (pinfunction "6_6") (pintype "passive+no_connect"))
    )
    (net (code "53") (name "unconnected-(J1-ID-PadP4)") (class "Default")
      (node (ref "J1") (pin "P4") (pinfunction "ID_P4") (pintype "passive+no_connect"))
    )
    (net (code "54") (name "unconnected-(J3-Pad1)") (class "Default")
      (node (ref "J3") (pin "1") (pinfunction "1_1") (pintype "passive+no_connect"))
    )
    (net (code "55") (name "unconnected-(ORIGIN-TESTP-PadX)") (class "Default")
      (node (ref "ORIGIN") (pin "X") (pinfunction "TESTP_X") (pintype "passive"))
    )
    (net (code "56") (name "unconnected-(RESET-5-GND-Pad5)") (class "Default")
      (node (ref "RESET") (pin "5") (pinfunction "5-GND_5") (pintype "passive"))
    )
    (net (code "57") (name "unconnected-(U3-NC{slash}FB-Pad4)") (class "Default")
      (node (ref "U3") (pin "4") (pinfunction "NC/FB_4") (pintype "passive"))
    )
  )
)
